# GSMRelay.net
KiCad netlist of a schematic drawn in Altium Designer
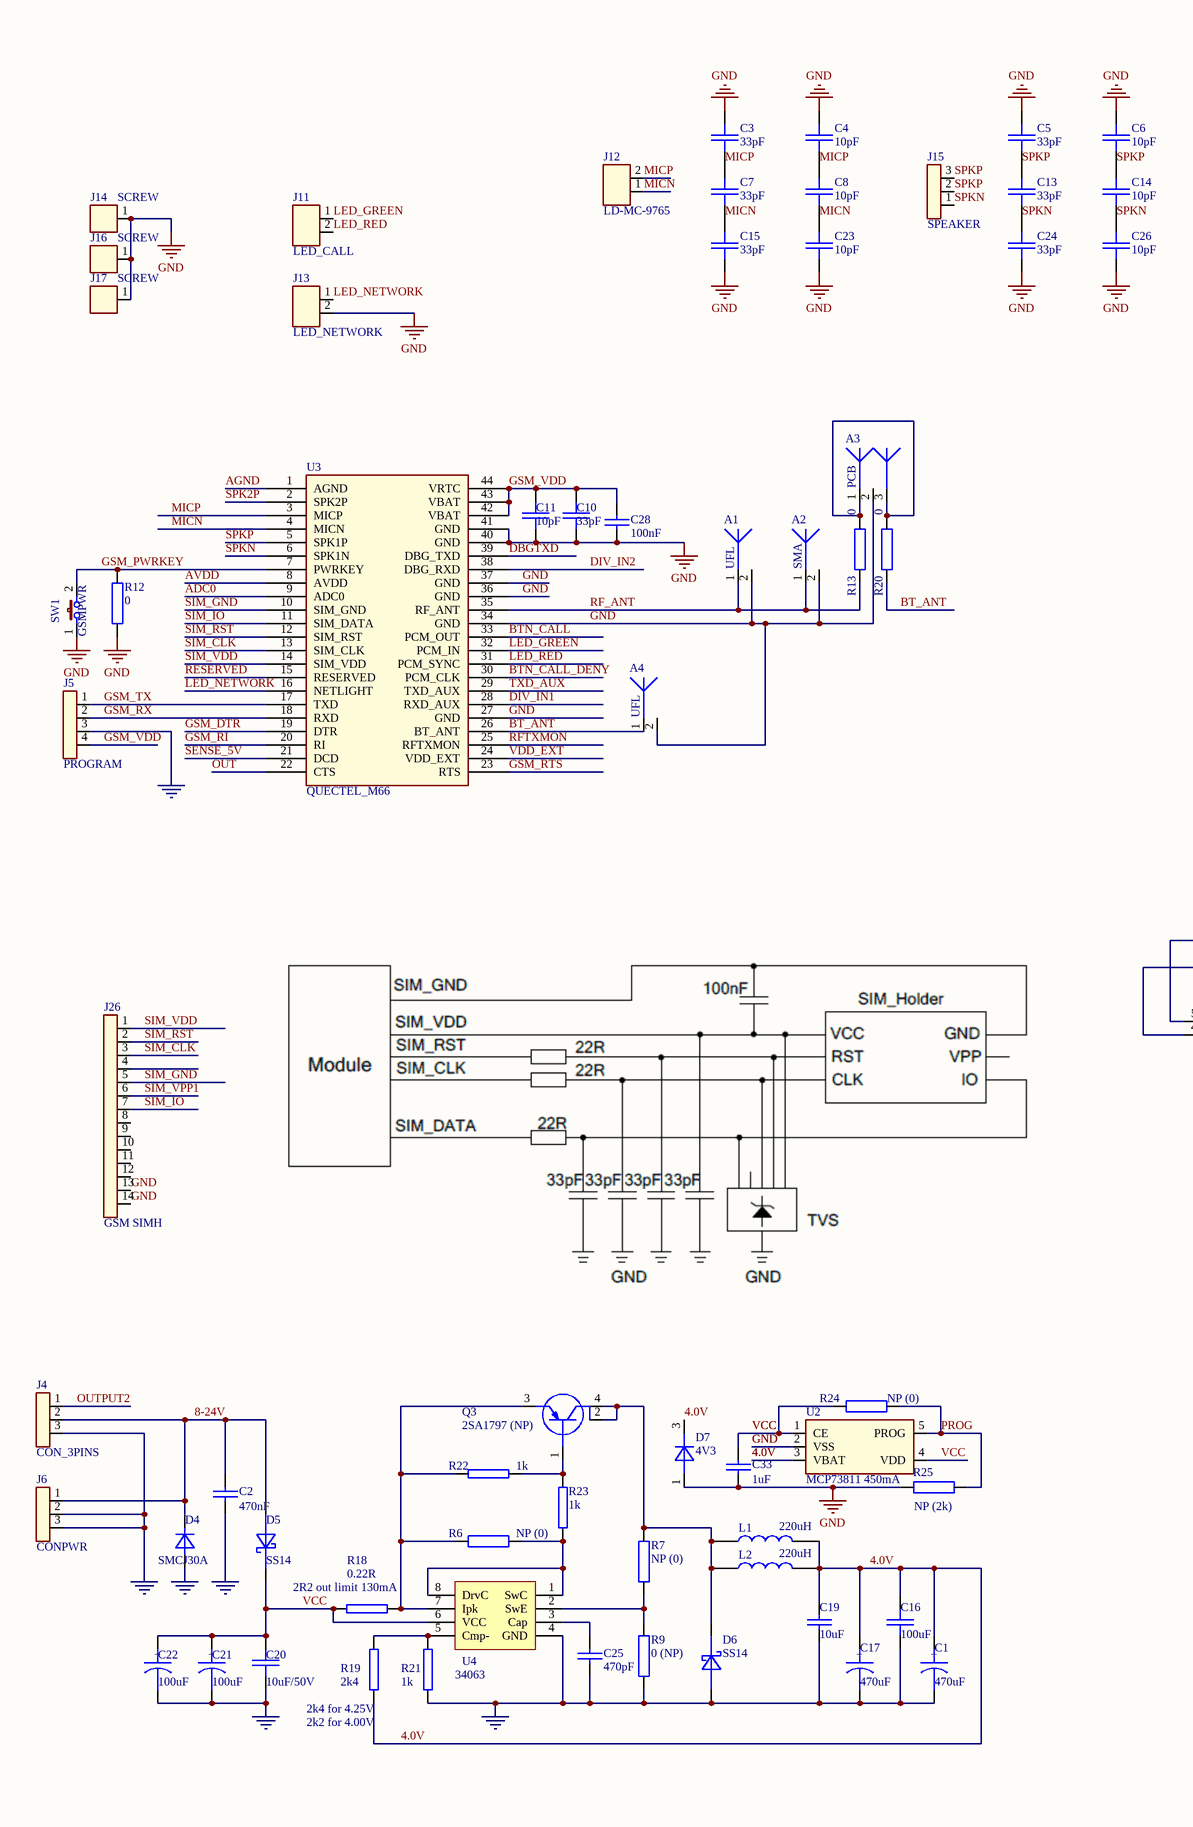
[diagram p0: GSMRelay.SchDoc, left]
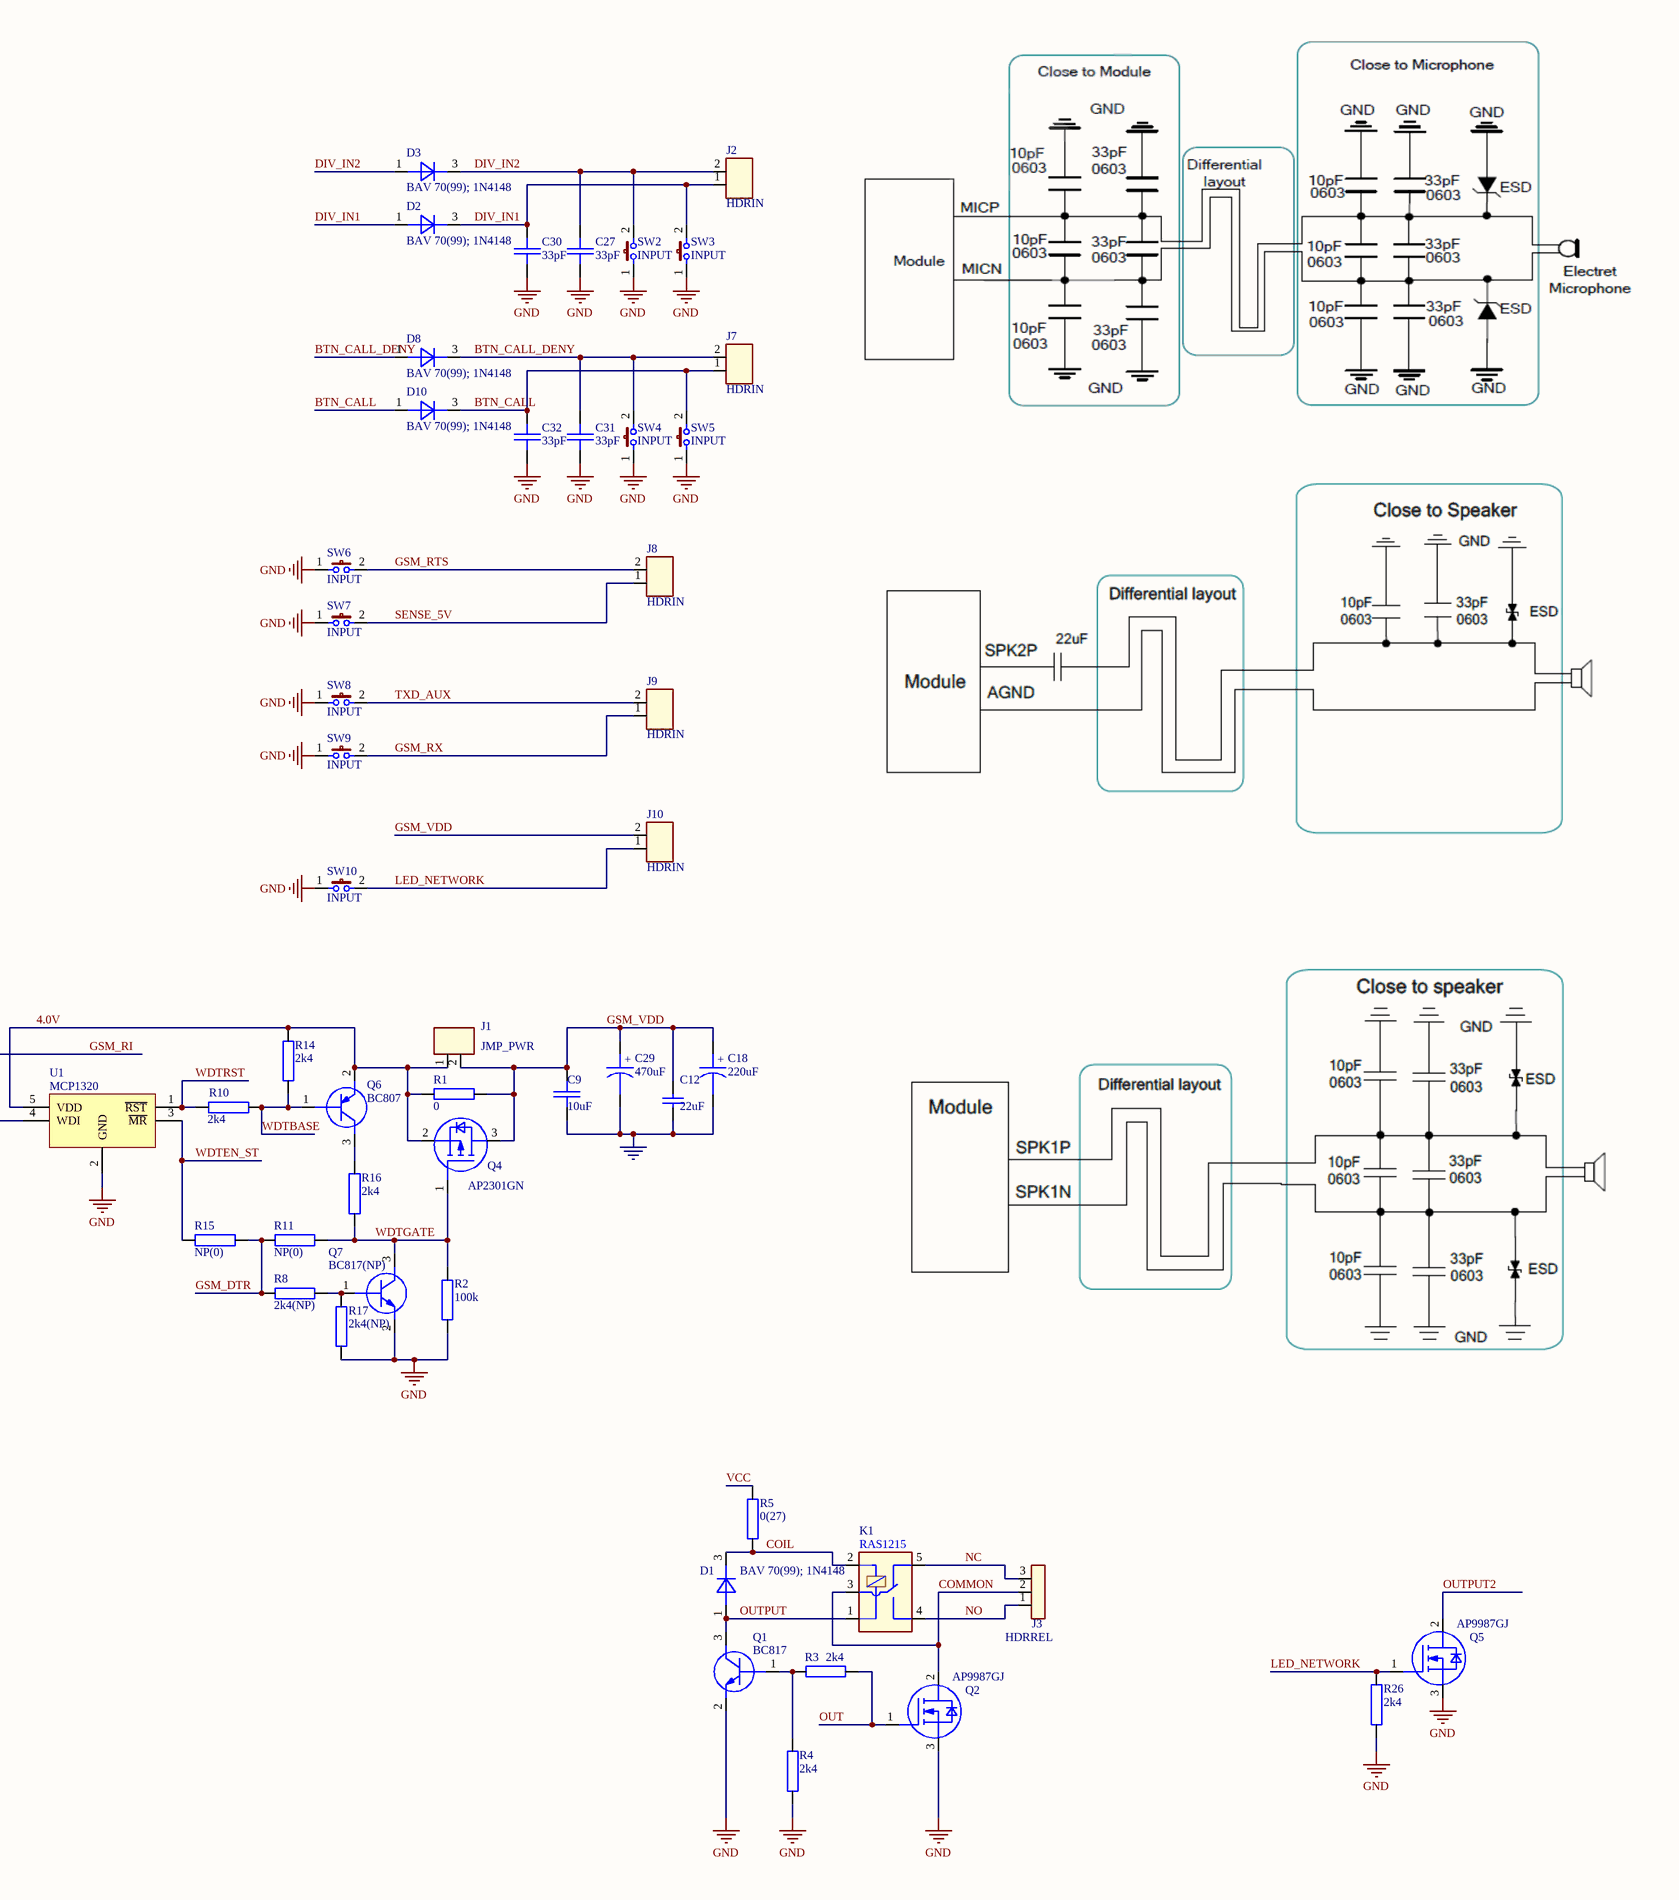
[diagram p1: GSMRelay.SchDoc, right]

(export (version "E")
  (design (tool "Eeschema 10.0.6"))
  (components
    (comp (ref "A1")
      (value "UFL")
      (footprint "SMD_CON_ANTENNA_UFL")
      (libsource (lib "DLV") (part "ANTENNA_2"))
    )
    (comp (ref "A2")
      (value "SMA")
      (footprint "SMD_CON_ANTENNA_SMA_RIGHT_ANGLE")
      (libsource (lib "DLV") (part "ANTENNA_2"))
    )
    (comp (ref "A3")
      (value "PCB")
      (footprint "SMD_CON_ANTENNA_GSM_WIFI_PCB")
      (libsource (lib "DLV") (part "ANTENNA_3"))
    )
    (comp (ref "A4")
      (value "UFL")
      (footprint "SMD_CON_ANTENNA_UFL")
      (libsource (lib "DLV") (part "ANTENNA_2"))
    )
    (comp (ref "C1")
      (value "470uF")
      (footprint "SMD_CAPAE660X550N")
      (description "Capacitor")
      (libsource (lib "*") (part "CAPACITOR POL"))
    )
    (comp (ref "C2")
      (value "470nF")
      (footprint "SMD_0603_CAPC1608X95N")
      (description "Capacitor")
      (libsource (lib "*") (part "CAP"))
    )
    (comp (ref "C3") (value "33pF") (footprint "SMD_0603_CAPC1608X95N") (libsource (lib "DLV") (part "C")))
    (comp (ref "C4") (value "10pF") (footprint "SMD_0603_CAPC1608X95N") (libsource (lib "DLV") (part "C")))
    (comp (ref "C5") (value "33pF") (footprint "SMD_0603_CAPC1608X95N") (libsource (lib "DLV") (part "C")))
    (comp (ref "C6") (value "10pF") (footprint "SMD_0603_CAPC1608X95N") (libsource (lib "DLV") (part "C")))
    (comp (ref "C7") (value "33pF") (footprint "SMD_0603_CAPC1608X95N") (libsource (lib "DLV") (part "C")))
    (comp (ref "C8") (value "10pF") (footprint "SMD_0603_CAPC1608X95N") (libsource (lib "DLV") (part "C")))
    (comp (ref "C9") (value "10uF") (footprint "SMD_0805_CAPC2012X95N") (libsource (lib "DLV") (part "C")))
    (comp (ref "C10") (value "33pF") (footprint "SMD_0603_CAPC1608X95N") (libsource (lib "DLV") (part "C")))
    (comp (ref "C11") (value "10pF") (footprint "SMD_0603_CAPC1608X95N") (libsource (lib "DLV") (part "C")))
    (comp (ref "C12")
      (value "22uF")
      (footprint "SMD_1210_CAPC3225X279N")
      (description "CL32A227MQVNNNE 220UF 6.3V 20% X5R 1210")
      (fields (field (name "PUBLISHER") "Altium Limited"))
      (libsource (lib "Miscellaneous Devices") (part "Cap Semi"))
    )
    (comp (ref "C13") (value "33pF") (footprint "SMD_0603_CAPC1608X95N") (libsource (lib "DLV") (part "C")))
    (comp (ref "C14") (value "10pF") (footprint "SMD_0603_CAPC1608X95N") (libsource (lib "DLV") (part "C")))
    (comp (ref "C15") (value "33pF") (footprint "SMD_0603_CAPC1608X95N") (libsource (lib "DLV") (part "C")))
    (comp (ref "C16") (value "100uF") (footprint "SMD_1210_CAPC3225X279N") (libsource (lib "DLV") (part "C")))
    (comp (ref "C17")
      (value "470uF")
      (footprint "PTH_CAPPR250-800X800")
      (description "Capacitor")
      (libsource (lib "*") (part "CAPACITOR POL"))
    )
    (comp (ref "C18")
      (value "220uF")
      (footprint "SMD_CAPAE660X550N")
      (description "Capacitor")
      (libsource (lib "") (part "CAPACITOR POL_1"))
    )
    (comp (ref "C19")
      (value "10uF")
      (footprint "SMD_0805_CAPC2012X95N")
      (description "Capacitor")
      (libsource (lib "*") (part "CAP"))
    )
    (comp (ref "C20")
      (value "10uF/50V")
      (footprint "SMD_1210_CAPC3225X279N")
      (libsource (lib "DLV") (part "C"))
    )
    (comp (ref "C21")
      (value "100uF")
      (footprint "SMD_CAPAE660X550N")
      (description "Capacitor")
      (libsource (lib "*") (part "CAPACITOR POL"))
    )
    (comp (ref "C22")
      (value "100uF")
      (footprint "PTH_CAPPR250-800X800")
      (description "Capacitor")
      (libsource (lib "*") (part "CAPACITOR POL"))
    )
    (comp (ref "C23") (value "10pF") (footprint "SMD_0603_CAPC1608X95N") (libsource (lib "DLV") (part "C")))
    (comp (ref "C24") (value "33pF") (footprint "SMD_0603_CAPC1608X95N") (libsource (lib "DLV") (part "C")))
    (comp (ref "C25")
      (value "470pF")
      (footprint "SMD_0603_CAPC1608X95N")
      (description "Capacitor")
      (libsource (lib "*") (part "CAP"))
    )
    (comp (ref "C26") (value "10pF") (footprint "SMD_0603_CAPC1608X95N") (libsource (lib "DLV") (part "C")))
    (comp (ref "C27") (value "33pF") (footprint "SMD_0603_CAPC1608X95N") (libsource (lib "DLV") (part "C")))
    (comp (ref "C28")
      (value "100nF")
      (footprint "SMD_0603_CAPC1608X95N")
      (description "Capacitor")
      (libsource (lib "*") (part "CAP"))
    )
    (comp (ref "C29")
      (value "470uF")
      (footprint "PTH_CAPPR250-800X800")
      (description "Capacitor")
      (libsource (lib "") (part "CAPACITOR POL_1"))
    )
    (comp (ref "C30") (value "33pF") (footprint "SMD_0603_CAPC1608X95N") (libsource (lib "DLV") (part "C")))
    (comp (ref "C31") (value "33pF") (footprint "SMD_0603_CAPC1608X95N") (libsource (lib "DLV") (part "C")))
    (comp (ref "C32") (value "33pF") (footprint "SMD_0603_CAPC1608X95N") (libsource (lib "DLV") (part "C")))
    (comp (ref "C33")
      (value "1uF")
      (footprint "SMD_0603_CAPC1608X95N")
      (description "Capacitor")
      (libsource (lib "*") (part "CAP"))
    )
    (comp (ref "D1")
      (value "BAV 70(99); 1N4148")
      (footprint "SMD_SOT23_SOT95P240X120-3N")
      (description "1N4148")
      (libsource (lib "DLV") (part "D_A1C3"))
    )
    (comp (ref "D2")
      (value "BAV 70(99); 1N4148")
      (footprint "SMD_SOT23_SOT95P240X120-3N")
      (description "1N4148")
      (libsource (lib "DLV") (part "D_A1C3"))
    )
    (comp (ref "D3")
      (value "BAV 70(99); 1N4148")
      (footprint "SMD_SOT23_SOT95P240X120-3N")
      (description "1N4148")
      (libsource (lib "DLV") (part "D_A1C3"))
    )
    (comp (ref "D4") (value "SMCJ30A") (footprint "SMD_DO214AC_SMC") (libsource (lib "DLV") (part "D")))
    (comp (ref "D5") (value "SS14") (footprint "SMD_DO214AC_SMA") (libsource (lib "BitCoin") (part "D_STKY")))
    (comp (ref "D6") (value "SS14") (footprint "SMD_DO214AC_SMA") (libsource (lib "BitCoin") (part "D_STKY")))
    (comp (ref "D7")
      (value "4V3")
      (footprint "SMD_SOT23_SOT95P240X120-3N")
      (description "1N4148")
      (libsource (lib "DLV") (part "D_A1C3"))
    )
    (comp (ref "D8")
      (value "BAV 70(99); 1N4148")
      (footprint "SMD_SOT23_SOT95P240X120-3N")
      (description "1N4148")
      (libsource (lib "DLV") (part "D_A1C3"))
    )
    (comp (ref "D10")
      (value "BAV 70(99); 1N4148")
      (footprint "SMD_SOT23_SOT95P240X120-3N")
      (description "1N4148")
      (libsource (lib "DLV") (part "D_A1C3"))
    )
    (comp (ref "J1")
      (value "JMP_PWR")
      (footprint "PTH_HDRV02W64P254_1X02")
      (libsource (lib "") (part "CON_2PINS_1"))
    )
    (comp (ref "J2")
      (value "HDRIN")
      (footprint "PTH_HDRV02W11060P500_1X02")
      (libsource (lib "") (part "CON_2PINS_1"))
    )
    (comp (ref "J3")
      (value "HDRREL")
      (footprint "PTH_HDRV03W11060P500_1X03")
      (libsource (lib "") (part "CON_3PINS_2"))
    )
    (comp (ref "J4")
      (value "CON_3PINS")
      (footprint "PTH_HDRV03W11060P500_1X03")
      (libsource (lib "DLV") (part "CON_3PINS"))
    )
    (comp (ref "J5")
      (value "PROGRAM")
      (footprint "PTH_HDRV04W64P254_1X04")
      (libsource (lib "DLV") (part "CON_4PINS"))
    )
    (comp (ref "J6")
      (value "CONPWR")
      (footprint "PTH_DC-POWER-JACK_210-112")
      (libsource (lib "DLV") (part "CON_3PINS"))
    )
    (comp (ref "J7")
      (value "HDRIN")
      (footprint "PTH_HDRV02W11060P500_1X02")
      (libsource (lib "") (part "CON_2PINS_1"))
    )
    (comp (ref "J8")
      (value "HDRIN")
      (footprint "PTH_HDRV02W11060P500_1X02")
      (libsource (lib "") (part "CON_2PINS_1"))
    )
    (comp (ref "J9")
      (value "HDRIN")
      (footprint "PTH_HDRV02W11060P500_1X02")
      (libsource (lib "") (part "CON_2PINS_1"))
    )
    (comp (ref "J10")
      (value "HDRIN")
      (footprint "PTH_HDRV02W11060P500_1X02")
      (libsource (lib "") (part "CON_2PINS_1"))
    )
    (comp (ref "J11")
      (value "LED_CALL")
      (footprint "PTH_LED-KINGBRIGHT-L-934SGC")
      (libsource (lib "DLV") (part "CON_2PINS"))
    )
    (comp (ref "J12")
      (value "LD-MC-9765")
      (footprint "PTH_MIC_9.6MM_6MM")
      (libsource (lib "") (part "CON_2PINS_2"))
    )
    (comp (ref "J13")
      (value "LED_NETWORK")
      (footprint "PTH_LED-KINGBRIGHT-L-934SGC")
      (libsource (lib "DLV") (part "CON_2PINS"))
    )
    (comp (ref "J14") (value "SCREW") (footprint "PTH_MOUNT_HOLE") (libsource (lib "DLV") (part "CON_1PIN")))
    (comp (ref "J15")
      (value "SPEAKER")
      (footprint "PTH_SPEAKER_MCABS-227-RC")
      (libsource (lib "") (part "CON_3PINS_1"))
    )
    (comp (ref "J16") (value "SCREW") (footprint "PTH_MOUNT_HOLE") (libsource (lib "DLV") (part "CON_1PIN")))
    (comp (ref "J17") (value "SCREW") (footprint "PTH_MOUNT_HOLE") (libsource (lib "DLV") (part "CON_1PIN")))
    (comp (ref "J26")
      (value "GSM SIMH")
      (footprint "SMD_CON-ATTEND_SIM_115B-AAA0-R01")
      (libsource (lib "DLV") (part "CON_14PINS"))
    )
    (comp (ref "K1") (value "RAS1215") (footprint "PTH_REL_RAS") (libsource (lib "DLV") (part "RELAY_SPDT")))
    (comp (ref "L1")
      (value "220uH")
      (footprint "SMD_INDM600500")
      (description "FPI0504 DA54")
      (libsource (lib "Miscellaneous Devices") (part "INDUCTOR1"))
    )
    (comp (ref "L2")
      (value "220uH")
      (footprint "PTH_CAPPR250-800X800")
      (libsource (lib "Miscellaneous Devices") (part "INDUCTOR1"))
    )
    (comp (ref "Q1")
      (value "BC817")
      (footprint "SMD_SOT23_SOT95P240X120-3N")
      (libsource (lib "DLV") (part "BJT_NPN_B1E2C3"))
    )
    (comp (ref "Q2")
      (value "AP9987GJ")
      (footprint "PTH_TO220AB")
      (libsource (lib "DLV") (part "MOS_N_D1_G1D2S3"))
    )
    (comp (ref "Q3")
      (value "2SA1797 (NP)")
      (footprint "SMD_SOT89_SOT150P400X130-4N")
      (libsource (lib "DLV") (part "BJT_PNP_B1C2E3C4"))
    )
    (comp (ref "Q4")
      (value "AP2301GN")
      (footprint "SMD_SOT23_SOT95P240X120-3N")
      (libsource (lib "DLV") (part "MOS_P_D1_G1S2D3"))
    )
    (comp (ref "Q5")
      (value "AP9987GJ")
      (footprint "PTH_TO220AB")
      (libsource (lib "DLV") (part "MOS_N_D1_G1D2S3"))
    )
    (comp (ref "Q6")
      (value "BC807")
      (footprint "SMD_SOT23_SOT95P240X120-3N")
      (libsource (lib "DLV") (part "BJT_PNP_B1E2C3"))
    )
    (comp (ref "Q7")
      (value "BC817(NP)")
      (footprint "SMD_SOT23_SOT95P240X120-3N")
      (libsource (lib "DLV") (part "BJT_NPN_B1E2C3"))
    )
    (comp (ref "R1") (value "0") (footprint "SMD_0603_RESC1608X55N") (libsource (lib "DLV") (part "R")))
    (comp (ref "R2") (value "100k") (footprint "SMD_0603_RESC1608X55N") (libsource (lib "DLV") (part "R")))
    (comp (ref "R3") (value "2k4") (footprint "SMD_0603_RESC1608X55N") (libsource (lib "DLV") (part "R")))
    (comp (ref "R4") (value "2k4") (footprint "SMD_0603_RESC1608X55N") (libsource (lib "DLV") (part "R")))
    (comp (ref "R5") (value "0(27)") (footprint "SMD_0603_RESC1608X55N") (libsource (lib "DLV") (part "R")))
    (comp (ref "R6") (value "NP (0)") (footprint "SMD_0603_RESC1608X55N") (libsource (lib "DLV") (part "R")))
    (comp (ref "R7") (value "NP (0)") (footprint "SMD_0603_RESC1608X55N") (libsource (lib "DLV") (part "R")))
    (comp (ref "R8") (value "2k4(NP)") (footprint "SMD_0603_RESC1608X55N") (libsource (lib "DLV") (part "R")))
    (comp (ref "R9") (value "0 (NP)") (footprint "SMD_0603_RESC1608X55N") (libsource (lib "DLV") (part "R")))
    (comp (ref "R10") (value "2k4") (footprint "SMD_0603_RESC1608X55N") (libsource (lib "DLV") (part "R")))
    (comp (ref "R11") (value "NP(0)") (footprint "SMD_0603_RESC1608X55N") (libsource (lib "DLV") (part "R")))
    (comp (ref "R12") (value "0") (footprint "SMD_0603_RESC1608X55N") (libsource (lib "DLV") (part "R")))
    (comp (ref "R13") (value "0") (footprint "SMD_0402_RESC1005X37N") (libsource (lib "DLV") (part "R")))
    (comp (ref "R14") (value "2k4") (footprint "SMD_0603_RESC1608X55N") (libsource (lib "DLV") (part "R")))
    (comp (ref "R15") (value "NP(0)") (footprint "SMD_0603_RESC1608X55N") (libsource (lib "DLV") (part "R")))
    (comp (ref "R16") (value "2k4") (footprint "SMD_0603_RESC1608X55N") (libsource (lib "DLV") (part "R")))
    (comp (ref "R17")
      (value "2k4(NP)")
      (footprint "SMD_0603_RESC1608X55N")
      (libsource (lib "DLV") (part "R"))
    )
    (comp (ref "R18")
      (value "0.22R")
      (footprint "SMD_0805_RESC2012X60N")
      (libsource (lib "Miscellaneous Devices") (part "RES2"))
    )
    (comp (ref "R19")
      (value "2k4")
      (footprint "SMD_0603_RESC1608X55N")
      (libsource (lib "Miscellaneous Devices") (part "RES2"))
    )
    (comp (ref "R20") (value "0") (footprint "SMD_0402_RESC1005X37N") (libsource (lib "DLV") (part "R")))
    (comp (ref "R21")
      (value "1k")
      (footprint "SMD_0603_RESC1608X55N")
      (libsource (lib "Miscellaneous Devices") (part "RES2"))
    )
    (comp (ref "R22")
      (value "1k")
      (footprint "SMD_0603_RESC1608X55N")
      (libsource (lib "Miscellaneous Devices") (part "RES2"))
    )
    (comp (ref "R23")
      (value "1k")
      (footprint "SMD_0603_RESC1608X55N")
      (libsource (lib "Miscellaneous Devices") (part "RES2"))
    )
    (comp (ref "R24") (value "NP (0)") (footprint "SMD_0603_RESC1608X55N") (libsource (lib "DLV") (part "R")))
    (comp (ref "R25")
      (value "NP (2k)")
      (footprint "SMD_0603_RESC1608X55N")
      (libsource (lib "DLV") (part "R"))
    )
    (comp (ref "R26") (value "2k4") (footprint "SMD_0603_RESC1608X55N") (libsource (lib "DLV") (part "R")))
    (comp (ref "SW1") (value "GSMPWR") (footprint "SMD_SW_DTSM-3") (libsource (lib "DLV") (part "BUTTON_3")))
    (comp (ref "SW2") (value "INPUT") (footprint "SMD_SW_DTSM-3") (libsource (lib "DLV") (part "BUTTON_3")))
    (comp (ref "SW3") (value "INPUT") (footprint "SMD_SW_DTSM-3") (libsource (lib "DLV") (part "BUTTON_3")))
    (comp (ref "SW4") (value "INPUT") (footprint "SMD_SW_DTSM-3") (libsource (lib "DLV") (part "BUTTON_3")))
    (comp (ref "SW5") (value "INPUT") (footprint "SMD_SW_DTSM-3") (libsource (lib "DLV") (part "BUTTON_3")))
    (comp (ref "SW6") (value "INPUT") (footprint "SMD_SW_DTSM-3") (libsource (lib "") (part "BUTTON_3_1")))
    (comp (ref "SW7") (value "INPUT") (footprint "SMD_SW_DTSM-3") (libsource (lib "") (part "BUTTON_3_1")))
    (comp (ref "SW8") (value "INPUT") (footprint "SMD_SW_DTSM-3") (libsource (lib "") (part "BUTTON_3_1")))
    (comp (ref "SW9") (value "INPUT") (footprint "SMD_SW_DTSM-3") (libsource (lib "") (part "BUTTON_3_1")))
    (comp (ref "SW10") (value "INPUT") (footprint "SMD_SW_DTSM-3") (libsource (lib "") (part "BUTTON_3_1")))
    (comp (ref "U1")
      (value "MCP1320")
      (footprint "SMD_SOT26_SOT95P285X140-5N - DLV")
      (description "Voltage Supervisor with Watchdog")
      (libsource (lib "DLV") (part "IC_MCP1320"))
    )
    (comp (ref "U2")
      (value "MCP73811 450mA")
      (footprint "SMD_SOT26_SOT95P285X140-5N - DLV")
      (description "MCP73812")
      (fields
        (field (name "DB_PART_NUMBER") "PSU000000127")
        (field (name "DB_MANUFACTURER_PART") "ROHM        BD33KA5WF-E2")
        (field (name "DB_APPROVED_BY") "VSN")
      )
      (libsource (lib "DLV") (part "IC_MCP73812"))
    )
    (comp (ref "U3")
      (value "QUECTEL_M66")
      (footprint "SMD_MOD_M66-44N")
      (libsource (lib "DLV") (part "MOD_QUECTEL_M66"))
    )
    (comp (ref "U4")
      (value "34063")
      (footprint "SMD_SOIC127P600X175-8N")
      (description "DC/DC converter")
      (libsource (lib "Devices") (part "34063"))
    )
  )
  (nets
    (net (code "1") (name "/4.0V") (class "Default")
      (node (ref "C1") (pin "1") (pinfunction "1_1") (pintype "passive"))
      (node (ref "C16") (pin "2") (pinfunction "2_2") (pintype "passive"))
      (node (ref "C17") (pin "1") (pinfunction "1_1") (pintype "passive"))
      (node (ref "C19") (pin "1") (pinfunction "1_1") (pintype "passive"))
      (node (ref "D7") (pin "3") (pinfunction "C_3") (pintype "passive"))
      (node (ref "J1") (pin "1") (pinfunction "1_1") (pintype "passive"))
      (node (ref "L1") (pin "2") (pinfunction "2_2") (pintype "passive"))
      (node (ref "L2") (pin "2") (pinfunction "2_2") (pintype "passive"))
      (node (ref "Q4") (pin "2") (pinfunction "S_2") (pintype "passive"))
      (node (ref "Q6") (pin "2") (pinfunction "E_2") (pintype "passive"))
      (node (ref "R1") (pin "1") (pinfunction "1_1") (pintype "passive"))
      (node (ref "R14") (pin "2") (pinfunction "2_2") (pintype "passive"))
      (node (ref "R19") (pin "1") (pinfunction "1_1") (pintype "passive"))
      (node (ref "U1") (pin "5") (pinfunction "VDD_5") (pintype "passive"))
      (node (ref "U2") (pin "3") (pinfunction "VBAT_3") (pintype "passive"))
    )
    (net (code "2") (name "/8-24V") (class "Default")
      (node (ref "C2") (pin "1") (pinfunction "1_1") (pintype "passive"))
      (node (ref "D4") (pin "1") (pinfunction "C_1") (pintype "passive"))
      (node (ref "D5") (pin "2") (pinfunction "A_2") (pintype "passive"))
      (node (ref "J4") (pin "2") (pinfunction "2_2") (pintype "passive"))
      (node (ref "J6") (pin "1") (pinfunction "1_1") (pintype "passive"))
    )
    (net (code "3") (name "/ADC0") (class "Default")
      (node (ref "U3") (pin "9") (pinfunction "ADC0_9") (pintype "passive"))
    )
    (net (code "4") (name "/AGND") (class "Default")
      (node (ref "U3") (pin "1") (pinfunction "AGND_1") (pintype "passive"))
    )
    (net (code "5") (name "/AVDD") (class "Default")
      (node (ref "U3") (pin "8") (pinfunction "AVDD_8") (pintype "passive"))
    )
    (net (code "6") (name "/BTN_CALL") (class "Default")
      (node (ref "C32") (pin "1") (pinfunction "1_1") (pintype "passive"))
      (node (ref "D10") (pin "1") (pinfunction "A_1") (pintype "passive"))
      (node (ref "D10") (pin "3") (pinfunction "C_3") (pintype "passive"))
      (node (ref "J7") (pin "1") (pinfunction "1_1") (pintype "passive"))
      (node (ref "SW5") (pin "2") (pinfunction "2_2") (pintype "passive"))
      (node (ref "U3") (pin "33") (pinfunction "PCM_OUT_33") (pintype "passive"))
    )
    (net (code "7") (name "/BTN_CALL_DENY") (class "Default")
      (node (ref "C31") (pin "1") (pinfunction "1_1") (pintype "passive"))
      (node (ref "D8") (pin "1") (pinfunction "A_1") (pintype "passive"))
      (node (ref "D8") (pin "3") (pinfunction "C_3") (pintype "passive"))
      (node (ref "J7") (pin "2") (pinfunction "2_2") (pintype "passive"))
      (node (ref "SW4") (pin "2") (pinfunction "2_2") (pintype "passive"))
      (node (ref "U3") (pin "30") (pinfunction "PCM_CLK_30") (pintype "passive"))
    )
    (net (code "8") (name "/BT_ANT") (class "Default")
      (node (ref "A4") (pin "1") (pinfunction "1_1") (pintype "passive"))
      (node (ref "R20") (pin "2") (pinfunction "2_2") (pintype "passive"))
      (node (ref "U3") (pin "26") (pinfunction "BT_ANT_26") (pintype "passive"))
    )
    (net (code "9") (name "/COIL") (class "Default")
      (node (ref "D1") (pin "3") (pinfunction "C_3") (pintype "passive"))
      (node (ref "K1") (pin "2") (pinfunction "2_2") (pintype "passive"))
      (node (ref "R5") (pin "1") (pinfunction "1_1") (pintype "passive"))
    )
    (net (code "10") (name "/COMMON") (class "Default")
      (node (ref "J3") (pin "2") (pinfunction "2_2") (pintype "passive"))
      (node (ref "K1") (pin "3") (pinfunction "3_3") (pintype "passive"))
      (node (ref "Q2") (pin "2") (pinfunction "D_2") (pintype "passive"))
    )
    (net (code "11") (name "/DBGTXD") (class "Default")
      (node (ref "U3") (pin "39") (pinfunction "DBG_TXD_39") (pintype "passive"))
    )
    (net (code "12") (name "/DIV_IN1") (class "Default")
      (node (ref "C30") (pin "1") (pinfunction "1_1") (pintype "passive"))
      (node (ref "D2") (pin "1") (pinfunction "A_1") (pintype "passive"))
      (node (ref "D2") (pin "3") (pinfunction "C_3") (pintype "passive"))
      (node (ref "J2") (pin "1") (pinfunction "1_1") (pintype "passive"))
      (node (ref "SW3") (pin "2") (pinfunction "2_2") (pintype "passive"))
      (node (ref "U3") (pin "28") (pinfunction "RXD_AUX_28") (pintype "passive"))
    )
    (net (code "13") (name "/DIV_IN2") (class "Default")
      (node (ref "C27") (pin "1") (pinfunction "1_1") (pintype "passive"))
      (node (ref "D3") (pin "1") (pinfunction "A_1") (pintype "passive"))
      (node (ref "D3") (pin "3") (pinfunction "C_3") (pintype "passive"))
      (node (ref "J2") (pin "2") (pinfunction "2_2") (pintype "passive"))
      (node (ref "SW2") (pin "2") (pinfunction "2_2") (pintype "passive"))
      (node (ref "U3") (pin "38") (pinfunction "DBG_RXD_38") (pintype "passive"))
    )
    (net (code "14") (name "/GSM_DTR") (class "Default")
      (node (ref "R11") (pin "2") (pinfunction "2_2") (pintype "passive"))
      (node (ref "R15") (pin "2") (pinfunction "2_2") (pintype "passive"))
      (node (ref "R8") (pin "1") (pinfunction "1_1") (pintype "passive"))
      (node (ref "U3") (pin "19") (pinfunction "DTR_19") (pintype "passive"))
    )
    (net (code "15") (name "/GSM_PWRKEY") (class "Default")
      (node (ref "R12") (pin "1") (pinfunction "1_1") (pintype "passive"))
      (node (ref "SW1") (pin "2") (pinfunction "2_2") (pintype "passive"))
      (node (ref "U3") (pin "7") (pinfunction "PWRKEY_7") (pintype "passive"))
    )
    (net (code "16") (name "/GSM_RI") (class "Default")
      (node (ref "U1") (pin "4") (pinfunction "WDI_4") (pintype "passive"))
      (node (ref "U3") (pin "20") (pinfunction "RI_20") (pintype "passive"))
    )
    (net (code "17") (name "/GSM_RTS") (class "Default")
      (node (ref "J8") (pin "2") (pinfunction "2_2") (pintype "passive"))
      (node (ref "SW6") (pin "2") (pinfunction "2_2") (pintype "passive"))
      (node (ref "U3") (pin "23") (pinfunction "RTS_23") (pintype "passive"))
    )
    (net (code "18") (name "/GSM_RX") (class "Default")
      (node (ref "J5") (pin "2") (pinfunction "2_2") (pintype "passive"))
      (node (ref "J9") (pin "1") (pinfunction "1_1") (pintype "passive"))
      (node (ref "SW9") (pin "2") (pinfunction "2_2") (pintype "passive"))
      (node (ref "U3") (pin "18") (pinfunction "RXD_18") (pintype "passive"))
    )
    (net (code "19") (name "/GSM_TX") (class "Default")
      (node (ref "J5") (pin "1") (pinfunction "1_1") (pintype "passive"))
      (node (ref "U3") (pin "17") (pinfunction "TXD_17") (pintype "passive"))
    )
    (net (code "20") (name "/GSM_VDD") (class "Default")
      (node (ref "C10") (pin "1") (pinfunction "1_1") (pintype "passive"))
      (node (ref "C11") (pin "1") (pinfunction "1_1") (pintype "passive"))
      (node (ref "C12") (pin "1") (pinfunction "1_1") (pintype "passive"))
      (node (ref "C18") (pin "1") (pinfunction "1_1") (pintype "passive"))
      (node (ref "C28") (pin "2") (pinfunction "2_2") (pintype "passive"))
      (node (ref "C29") (pin "1") (pinfunction "1_1") (pintype "passive"))
      (node (ref "C9") (pin "1") (pinfunction "1_1") (pintype "passive"))
      (node (ref "J1") (pin "2") (pinfunction "2_2") (pintype "passive"))
      (node (ref "J10") (pin "2") (pinfunction "2_2") (pintype "passive"))
      (node (ref "J5") (pin "4") (pinfunction "4_4") (pintype "passive"))
      (node (ref "Q4") (pin "3") (pinfunction "D_3") (pintype "passive"))
      (node (ref "R1") (pin "2") (pinfunction "2_2") (pintype "passive"))
      (node (ref "U3") (pin "42") (pinfunction "VBAT_42") (pintype "passive"))
      (node (ref "U3") (pin "43") (pinfunction "VBAT_43") (pintype "passive"))
      (node (ref "U3") (pin "44") (pinfunction "VRTC_44") (pintype "passive"))
    )
    (net (code "21") (name "/LED_GREEN") (class "Default")
      (node (ref "J11") (pin "1") (pinfunction "1_1") (pintype "passive"))
      (node (ref "U3") (pin "32") (pinfunction "PCM_IN_32") (pintype "passive"))
    )
    (net (code "22") (name "/LED_NETWORK") (class "Default")
      (node (ref "J10") (pin "1") (pinfunction "1_1") (pintype "passive"))
      (node (ref "J13") (pin "1") (pinfunction "1_1") (pintype "passive"))
      (node (ref "Q5") (pin "1") (pinfunction "G_1") (pintype "passive"))
      (node (ref "R26") (pin "1") (pinfunction "1_1") (pintype "passive"))
      (node (ref "SW10") (pin "2") (pinfunction "2_2") (pintype "passive"))
      (node (ref "U3") (pin "16") (pinfunction "NETLIGHT_16") (pintype "passive"))
    )
    (net (code "23") (name "/LED_RED") (class "Default")
      (node (ref "J11") (pin "2") (pinfunction "2_2") (pintype "passive"))
      (node (ref "U3") (pin "31") (pinfunction "PCM_SYNC_31") (pintype "passive"))
    )
    (net (code "24") (name "/MICN") (class "Default")
      (node (ref "C15") (pin "1") (pinfunction "1_1") (pintype "passive"))
      (node (ref "C23") (pin "1") (pinfunction "1_1") (pintype "passive"))
      (node (ref "C7") (pin "2") (pinfunction "2_2") (pintype "passive"))
      (node (ref "C8") (pin "2") (pinfunction "2_2") (pintype "passive"))
      (node (ref "J12") (pin "1") (pinfunction "1_1") (pintype "passive"))
      (node (ref "U3") (pin "4") (pinfunction "MICN_4") (pintype "passive"))
    )
    (net (code "25") (name "/MICP") (class "Default")
      (node (ref "C3") (pin "2") (pinfunction "2_2") (pintype "passive"))
      (node (ref "C4") (pin "2") (pinfunction "2_2") (pintype "passive"))
      (node (ref "C7") (pin "1") (pinfunction "1_1") (pintype "passive"))
      (node (ref "C8") (pin "1") (pinfunction "1_1") (pintype "passive"))
      (node (ref "J12") (pin "2") (pinfunction "2_2") (pintype "passive"))
      (node (ref "U3") (pin "3") (pinfunction "MICP_3") (pintype "passive"))
    )
    (net (code "26") (name "/NC") (class "Default")
      (node (ref "J3") (pin "3") (pinfunction "3_3") (pintype "passive"))
      (node (ref "K1") (pin "5") (pinfunction "5_5") (pintype "passive"))
    )
    (net (code "27") (name "/NO") (class "Default")
      (node (ref "J3") (pin "1") (pinfunction "1_1") (pintype "passive"))
      (node (ref "K1") (pin "4") (pinfunction "4_4") (pintype "passive"))
    )
    (net (code "28") (name "/OUT") (class "Default")
      (node (ref "Q2") (pin "1") (pinfunction "G_1") (pintype "passive"))
      (node (ref "R3") (pin "2") (pinfunction "2_2") (pintype "passive"))
      (node (ref "U3") (pin "22") (pinfunction "CTS_22") (pintype "passive"))
    )
    (net (code "29") (name "/OUTPUT") (class "Default")
      (node (ref "D1") (pin "1") (pinfunction "A_1") (pintype "passive"))
      (node (ref "K1") (pin "1") (pinfunction "1_1") (pintype "passive"))
      (node (ref "Q1") (pin "3") (pinfunction "C_3") (pintype "passive"))
    )
    (net (code "30") (name "/OUTPUT2") (class "Default")
      (node (ref "J4") (pin "1") (pinfunction "1_1") (pintype "passive"))
      (node (ref "Q5") (pin "2") (pinfunction "D_2") (pintype "passive"))
    )
    (net (code "31") (name "/PROG") (class "Default")
      (node (ref "R24") (pin "2") (pinfunction "2_2") (pintype "passive"))
      (node (ref "R25") (pin "1") (pinfunction "1_1") (pintype "passive"))
      (node (ref "U2") (pin "5") (pinfunction "PROG_5") (pintype "passive"))
    )
    (net (code "32") (name "/RESERVED") (class "Default")
      (node (ref "U3") (pin "15") (pinfunction "RESERVED_15") (pintype "passive"))
    )
    (net (code "33") (name "/RFTXMON") (class "Default")
      (node (ref "U3") (pin "25") (pinfunction "RFTXMON_25") (pintype "passive"))
    )
    (net (code "34") (name "/RF_ANT") (class "Default")
      (node (ref "A1") (pin "1") (pinfunction "1_1") (pintype "passive"))
      (node (ref "A2") (pin "1") (pinfunction "1_1") (pintype "passive"))
      (node (ref "R13") (pin "2") (pinfunction "2_2") (pintype "passive"))
      (node (ref "U3") (pin "35") (pinfunction "RF_ANT_35") (pintype "passive"))
    )
    (net (code "35") (name "/SENSE_5V") (class "Default")
      (node (ref "J8") (pin "1") (pinfunction "1_1") (pintype "passive"))
      (node (ref "SW7") (pin "2") (pinfunction "2_2") (pintype "passive"))
      (node (ref "U3") (pin "21") (pinfunction "DCD_21") (pintype "passive"))
    )
    (net (code "36") (name "/SIM_CLK") (class "Default")
      (node (ref "J26") (pin "3") (pinfunction "3_3") (pintype "passive"))
      (node (ref "U3") (pin "13") (pinfunction "SIM_CLK_13") (pintype "passive"))
    )
    (net (code "37") (name "/SIM_GND") (class "Default")
      (node (ref "J26") (pin "5") (pinfunction "5_5") (pintype "passive"))
      (node (ref "U3") (pin "10") (pinfunction "SIM_GND_10") (pintype "passive"))
    )
    (net (code "38") (name "/SIM_IO") (class "Default")
      (node (ref "J26") (pin "7") (pinfunction "7_7") (pintype "passive"))
      (node (ref "U3") (pin "11") (pinfunction "SIM_DATA_11") (pintype "passive"))
    )
    (net (code "39") (name "/SIM_RST") (class "Default")
      (node (ref "J26") (pin "2") (pinfunction "2_2") (pintype "passive"))
      (node (ref "U3") (pin "12") (pinfunction "SIM_RST_12") (pintype "passive"))
    )
    (net (code "40") (name "/SIM_VDD") (class "Default")
      (node (ref "J26") (pin "1") (pinfunction "1_1") (pintype "passive"))
      (node (ref "U3") (pin "14") (pinfunction "SIM_VDD_14") (pintype "passive"))
    )
    (net (code "41") (name "/SIM_VPP1") (class "Default")
      (node (ref "J26") (pin "6") (pinfunction "6_6") (pintype "passive"))
    )
    (net (code "42") (name "/SPK2P") (class "Default")
      (node (ref "U3") (pin "2") (pinfunction "SPK2P_2") (pintype "passive"))
    )
    (net (code "43") (name "/SPKN") (class "Default")
      (node (ref "C13") (pin "2") (pinfunction "2_2") (pintype "passive"))
      (node (ref "C14") (pin "2") (pinfunction "2_2") (pintype "passive"))
      (node (ref "C24") (pin "1") (pinfunction "1_1") (pintype "passive"))
      (node (ref "C26") (pin "1") (pinfunction "1_1") (pintype "passive"))
      (node (ref "J15") (pin "1") (pinfunction "1_1") (pintype "passive"))
      (node (ref "U3") (pin "6") (pinfunction "SPK1N_6") (pintype "passive"))
    )
    (net (code "44") (name "/SPKP") (class "Default")
      (node (ref "C13") (pin "1") (pinfunction "1_1") (pintype "passive"))
      (node (ref "C14") (pin "1") (pinfunction "1_1") (pintype "passive"))
      (node (ref "C5") (pin "2") (pinfunction "2_2") (pintype "passive"))
      (node (ref "C6") (pin "2") (pinfunction "2_2") (pintype "passive"))
      (node (ref "J15") (pin "2") (pinfunction "2_2") (pintype "passive"))
      (node (ref "J15") (pin "3") (pinfunction "3_3") (pintype "passive"))
      (node (ref "U3") (pin "5") (pinfunction "SPK1P_5") (pintype "passive"))
    )
    (net (code "45") (name "/TXD_AUX") (class "Default")
      (node (ref "J9") (pin "2") (pinfunction "2_2") (pintype "passive"))
      (node (ref "SW8") (pin "2") (pinfunction "2_2") (pintype "passive"))
      (node (ref "U3") (pin "29") (pinfunction "TXD_AUX_29") (pintype "passive"))
    )
    (net (code "46") (name "/VCC") (class "Default")
      (node (ref "C20") (pin "2") (pinfunction "2_2") (pintype "passive"))
      (node (ref "C21") (pin "1") (pinfunction "1_1") (pintype "passive"))
      (node (ref "C22") (pin "1") (pinfunction "1_1") (pintype "passive"))
      (node (ref "C33") (pin "2") (pinfunction "2_2") (pintype "passive"))
      (node (ref "D5") (pin "1") (pinfunction "C_1") (pintype "passive"))
      (node (ref "R18") (pin "2") (pinfunction "2_2") (pintype "passive"))
      (node (ref "R24") (pin "1") (pinfunction "1_1") (pintype "passive"))
      (node (ref "R5") (pin "2") (pinfunction "2_2") (pintype "passive"))
      (node (ref "U2") (pin "1") (pinfunction "CE_1") (pintype "passive"))
      (node (ref "U2") (pin "4") (pinfunction "VDD_4") (pintype "passive"))
      (node (ref "U4") (pin "6") (pinfunction "VCC_6") (pintype "passive"))
    )
    (net (code "47") (name "/VDD_EXT") (class "Default")
      (node (ref "U3") (pin "24") (pinfunction "VDD_EXT_24") (pintype "passive"))
    )
    (net (code "48") (name "/WDTBASE") (class "Default")
      (node (ref "Q6") (pin "1") (pinfunction "B_1") (pintype "passive"))
      (node (ref "R10") (pin "2") (pinfunction "2_2") (pintype "passive"))
      (node (ref "R14") (pin "1") (pinfunction "1_1") (pintype "passive"))
    )
    (net (code "49") (name "/WDTEN_ST") (class "Default")
      (node (ref "R15") (pin "1") (pinfunction "1_1") (pintype "passive"))
      (node (ref "U1") (pin "3") (pinfunction "~{MR}_3") (pintype "passive"))
    )
    (net (code "50") (name "/WDTGATE") (class "Default")
      (node (ref "Q4") (pin "1") (pinfunction "G_1") (pintype "passive"))
      (node (ref "Q7") (pin "3") (pinfunction "C_3") (pintype "passive"))
      (node (ref "R11") (pin "1") (pinfunction "1_1") (pintype "passive"))
      (node (ref "R16") (pin "1") (pinfunction "1_1") (pintype "passive"))
      (node (ref "R2") (pin "2") (pinfunction "2_2") (pintype "passive"))
    )
    (net (code "51") (name "/WDTRST") (class "Default")
      (node (ref "R10") (pin "1") (pinfunction "1_1") (pintype "passive"))
      (node (ref "U1") (pin "1") (pinfunction "~{RST}_1") (pintype "passive"))
    )
    (net (code "52") (name "GND") (class "Default")
      (node (ref "A1") (pin "2") (pinfunction "2_2") (pintype "passive"))
      (node (ref "A2") (pin "2") (pinfunction "2_2") (pintype "passive"))
      (node (ref "A3") (pin "2") (pinfunction "2_2") (pintype "passive"))
      (node (ref "A4") (pin "2") (pinfunction "2_2") (pintype "passive"))
      (node (ref "C1") (pin "2") (pinfunction "2_2") (pintype "passive"))
      (node (ref "C10") (pin "2") (pinfunction "2_2") (pintype "passive"))
      (node (ref "C11") (pin "2") (pinfunction "2_2") (pintype "passive"))
      (node (ref "C12") (pin "2") (pinfunction "2_2") (pintype "passive"))
      (node (ref "C15") (pin "2") (pinfunction "2_2") (pintype "passive"))
      (node (ref "C16") (pin "1") (pinfunction "1_1") (pintype "passive"))
      (node (ref "C17") (pin "2") (pinfunction "2_2") (pintype "passive"))
      (node (ref "C18") (pin "2") (pinfunction "2_2") (pintype "passive"))
      (node (ref "C19") (pin "2") (pinfunction "2_2") (pintype "passive"))
      (node (ref "C2") (pin "2") (pinfunction "2_2") (pintype "passive"))
      (node (ref "C20") (pin "1") (pinfunction "1_1") (pintype "passive"))
      (node (ref "C21") (pin "2") (pinfunction "2_2") (pintype "passive"))
      (node (ref "C22") (pin "2") (pinfunction "2_2") (pintype "passive"))
      (node (ref "C23") (pin "2") (pinfunction "2_2") (pintype "passive"))
      (node (ref "C24") (pin "2") (pinfunction "2_2") (pintype "passive"))
      (node (ref "C25") (pin "2") (pinfunction "2_2") (pintype "passive"))
      (node (ref "C26") (pin "2") (pinfunction "2_2") (pintype "passive"))
      (node (ref "C27") (pin "2") (pinfunction "2_2") (pintype "passive"))
      (node (ref "C28") (pin "1") (pinfunction "1_1") (pintype "passive"))
      (node (ref "C29") (pin "2") (pinfunction "2_2") (pintype "passive"))
      (node (ref "C3") (pin "1") (pinfunction "1_1") (pintype "passive"))
      (node (ref "C30") (pin "2") (pinfunction "2_2") (pintype "passive"))
      (node (ref "C31") (pin "2") (pinfunction "2_2") (pintype "passive"))
      (node (ref "C32") (pin "2") (pinfunction "2_2") (pintype "passive"))
      (node (ref "C33") (pin "1") (pinfunction "1_1") (pintype "passive"))
      (node (ref "C4") (pin "1") (pinfunction "1_1") (pintype "passive"))
      (node (ref "C5") (pin "1") (pinfunction "1_1") (pintype "passive"))
      (node (ref "C6") (pin "1") (pinfunction "1_1") (pintype "passive"))
      (node (ref "C9") (pin "2") (pinfunction "2_2") (pintype "passive"))
      (node (ref "D4") (pin "2") (pinfunction "A_2") (pintype "passive"))
      (node (ref "D6") (pin "2") (pinfunction "A_2") (pintype "passive"))
      (node (ref "D7") (pin "1") (pinfunction "A_1") (pintype "passive"))
      (node (ref "J13") (pin "2") (pinfunction "2_2") (pintype "passive"))
      (node (ref "J14") (pin "1") (pinfunction "1_1") (pintype "passive"))
      (node (ref "J16") (pin "1") (pinfunction "1_1") (pintype "passive"))
      (node (ref "J17") (pin "1") (pinfunction "1_1") (pintype "passive"))
      (node (ref "J26") (pin "13") (pinfunction "13_13") (pintype "passive"))
      (node (ref "J26") (pin "14") (pinfunction "14_14") (pintype "passive"))
      (node (ref "J4") (pin "3") (pinfunction "3_3") (pintype "passive"))
      (node (ref "J5") (pin "3") (pinfunction "3_3") (pintype "passive"))
      (node (ref "J6") (pin "2") (pinfunction "2_2") (pintype "passive"))
      (node (ref "J6") (pin "3") (pinfunction "3_3") (pintype "passive"))
      (node (ref "Q1") (pin "2") (pinfunction "E_2") (pintype "passive"))
      (node (ref "Q2") (pin "3") (pinfunction "S_3") (pintype "passive"))
      (node (ref "Q5") (pin "3") (pinfunction "S_3") (pintype "passive"))
      (node (ref "Q7") (pin "2") (pinfunction "E_2") (pintype "passive"))
      (node (ref "R12") (pin "2") (pinfunction "2_2") (pintype "passive"))
      (node (ref "R17") (pin "1") (pinfunction "1_1") (pintype "passive"))
      (node (ref "R2") (pin "1") (pinfunction "1_1") (pintype "passive"))
      (node (ref "R21") (pin "2") (pinfunction "2_2") (pintype "passive"))
      (node (ref "R25") (pin "2") (pinfunction "2_2") (pintype "passive"))
      (node (ref "R26") (pin "2") (pinfunction "2_2") (pintype "passive"))
      (node (ref "R4") (pin "2") (pinfunction "2_2") (pintype "passive"))
      (node (ref "R9") (pin "1") (pinfunction "1_1") (pintype "passive"))
      (node (ref "SW1") (pin "1") (pinfunction "1_1") (pintype "passive"))
      (node (ref "SW10") (pin "1") (pinfunction "1_1") (pintype "passive"))
      (node (ref "SW2") (pin "1") (pinfunction "1_1") (pintype "passive"))
      (node (ref "SW3") (pin "1") (pinfunction "1_1") (pintype "passive"))
      (node (ref "SW4") (pin "1") (pinfunction "1_1") (pintype "passive"))
      (node (ref "SW5") (pin "1") (pinfunction "1_1") (pintype "passive"))
      (node (ref "SW6") (pin "1") (pinfunction "1_1") (pintype "passive"))
      (node (ref "SW7") (pin "1") (pinfunction "1_1") (pintype "passive"))
      (node (ref "SW8") (pin "1") (pinfunction "1_1") (pintype "passive"))
      (node (ref "SW9") (pin "1") (pinfunction "1_1") (pintype "passive"))
      (node (ref "U1") (pin "2") (pinfunction "GND_2") (pintype "passive"))
      (node (ref "U2") (pin "2") (pinfunction "VSS_2") (pintype "passive"))
      (node (ref "U3") (pin "27") (pinfunction "GND_27") (pintype "passive"))
      (node (ref "U3") (pin "34") (pinfunction "GND_34") (pintype "passive"))
      (node (ref "U3") (pin "36") (pinfunction "GND_36") (pintype "passive"))
      (node (ref "U3") (pin "37") (pinfunction "GND_37") (pintype "passive"))
      (node (ref "U3") (pin "40") (pinfunction "GND_40") (pintype "passive"))
      (node (ref "U3") (pin "41") (pinfunction "GND_41") (pintype "passive"))
      (node (ref "U4") (pin "4") (pinfunction "GND_4") (pintype "passive"))
    )
    (net (code "53") (name "Net-(A3-Pad1)") (class "Default")
      (node (ref "A3") (pin "1") (pinfunction "1_1") (pintype "passive"))
      (node (ref "A3") (pin "3") (pinfunction "3_3") (pintype "passive"))
      (node (ref "R13") (pin "1") (pinfunction "1_1") (pintype "passive"))
      (node (ref "R20") (pin "1") (pinfunction "1_1") (pintype "passive"))
    )
    (net (code "54") (name "Net-(D6-C)") (class "Default")
      (node (ref "D6") (pin "1") (pinfunction "C_1") (pintype "passive"))
      (node (ref "L1") (pin "1") (pinfunction "1_1") (pintype "passive"))
      (node (ref "L2") (pin "1") (pinfunction "1_1") (pintype "passive"))
      (node (ref "Q3") (pin "2") (pinfunction "E_2") (pintype "passive"))
      (node (ref "Q3") (pin "4") (pinfunction "C_4") (pintype "passive"))
      (node (ref "R7") (pin "2") (pinfunction "2_2") (pintype "passive"))
    )
    (net (code "55") (name "Net-(Q1-B)") (class "Default")
      (node (ref "Q1") (pin "1") (pinfunction "B_1") (pintype "passive"))
      (node (ref "R3") (pin "1") (pinfunction "1_1") (pintype "passive"))
      (node (ref "R4") (pin "1") (pinfunction "1_1") (pintype "passive"))
    )
    (net (code "56") (name "Net-(Q3-B)") (class "Default")
      (node (ref "Q3") (pin "1") (pinfunction "B_1") (pintype "passive"))
      (node (ref "R22") (pin "2") (pinfunction "2_2") (pintype "passive"))
      (node (ref "R23") (pin "1") (pinfunction "1_1") (pintype "passive"))
    )
    (net (code "57") (name "Net-(Q6-C)") (class "Default")
      (node (ref "Q6") (pin "3") (pinfunction "C_3") (pintype "passive"))
      (node (ref "R16") (pin "2") (pinfunction "2_2") (pintype "passive"))
    )
    (net (code "58") (name "Net-(Q7-B)") (class "Default")
      (node (ref "Q7") (pin "1") (pinfunction "B_1") (pintype "passive"))
      (node (ref "R17") (pin "2") (pinfunction "2_2") (pintype "passive"))
      (node (ref "R8") (pin "2") (pinfunction "2_2") (pintype "passive"))
    )
    (net (code "59") (name "Net-(U4-Cap)") (class "Default")
      (node (ref "C25") (pin "1") (pinfunction "1_1") (pintype "passive"))
      (node (ref "U4") (pin "3") (pinfunction "Cap_3") (pintype "passive"))
    )
    (net (code "60") (name "Net-(U4-Cmp-)") (class "Default")
      (node (ref "R19") (pin "2") (pinfunction "2_2") (pintype "passive"))
      (node (ref "R21") (pin "1") (pinfunction "1_1") (pintype "passive"))
      (node (ref "U4") (pin "5") (pinfunction "Cmp-_5") (pintype "passive"))
    )
    (net (code "61") (name "Net-(U4-DrvC)") (class "Default")
      (node (ref "R23") (pin "2") (pinfunction "2_2") (pintype "passive"))
      (node (ref "R6") (pin "1") (pinfunction "1_1") (pintype "passive"))
      (node (ref "U4") (pin "1") (pinfunction "SwC_1") (pintype "passive"))
      (node (ref "U4") (pin "8") (pinfunction "DrvC_8") (pintype "passive"))
    )
    (net (code "62") (name "Net-(U4-Ipk)") (class "Default")
      (node (ref "Q3") (pin "3") (pinfunction "C_3") (pintype "passive"))
      (node (ref "R18") (pin "1") (pinfunction "1_1") (pintype "passive"))
      (node (ref "R22") (pin "1") (pinfunction "1_1") (pintype "passive"))
      (node (ref "R6") (pin "2") (pinfunction "2_2") (pintype "passive"))
      (node (ref "U4") (pin "7") (pinfunction "Ipk_7") (pintype "passive"))
    )
    (net (code "63") (name "Net-(U4-SwE)") (class "Default")
      (node (ref "R7") (pin "1") (pinfunction "1_1") (pintype "passive"))
      (node (ref "R9") (pin "2") (pinfunction "2_2") (pintype "passive"))
      (node (ref "U4") (pin "2") (pinfunction "SwE_2") (pintype "passive"))
    )
    (net (code "64") (name "unconnected-(J26-Pad4)") (class "Default")
      (node (ref "J26") (pin "4") (pinfunction "4_4") (pintype "passive"))
    )
    (net (code "65") (name "unconnected-(J26-Pad8)") (class "Default")
      (node (ref "J26") (pin "8") (pinfunction "8_8") (pintype "passive"))
    )
    (net (code "66") (name "unconnected-(J26-Pad9)") (class "Default")
      (node (ref "J26") (pin "9") (pinfunction "9_9") (pintype "passive"))
    )
    (net (code "67") (name "unconnected-(J26-Pad10)") (class "Default")
      (node (ref "J26") (pin "10") (pinfunction "10_10") (pintype "passive"))
    )
    (net (code "68") (name "unconnected-(J26-Pad11)") (class "Default")
      (node (ref "J26") (pin "11") (pinfunction "11_11") (pintype "passive"))
    )
    (net (code "69") (name "unconnected-(J26-Pad12)") (class "Default")
      (node (ref "J26") (pin "12") (pinfunction "12_12") (pintype "passive"))
    )
  )
)
